# POWER.net
KiCad netlist of a schematic drawn in Altium Designer
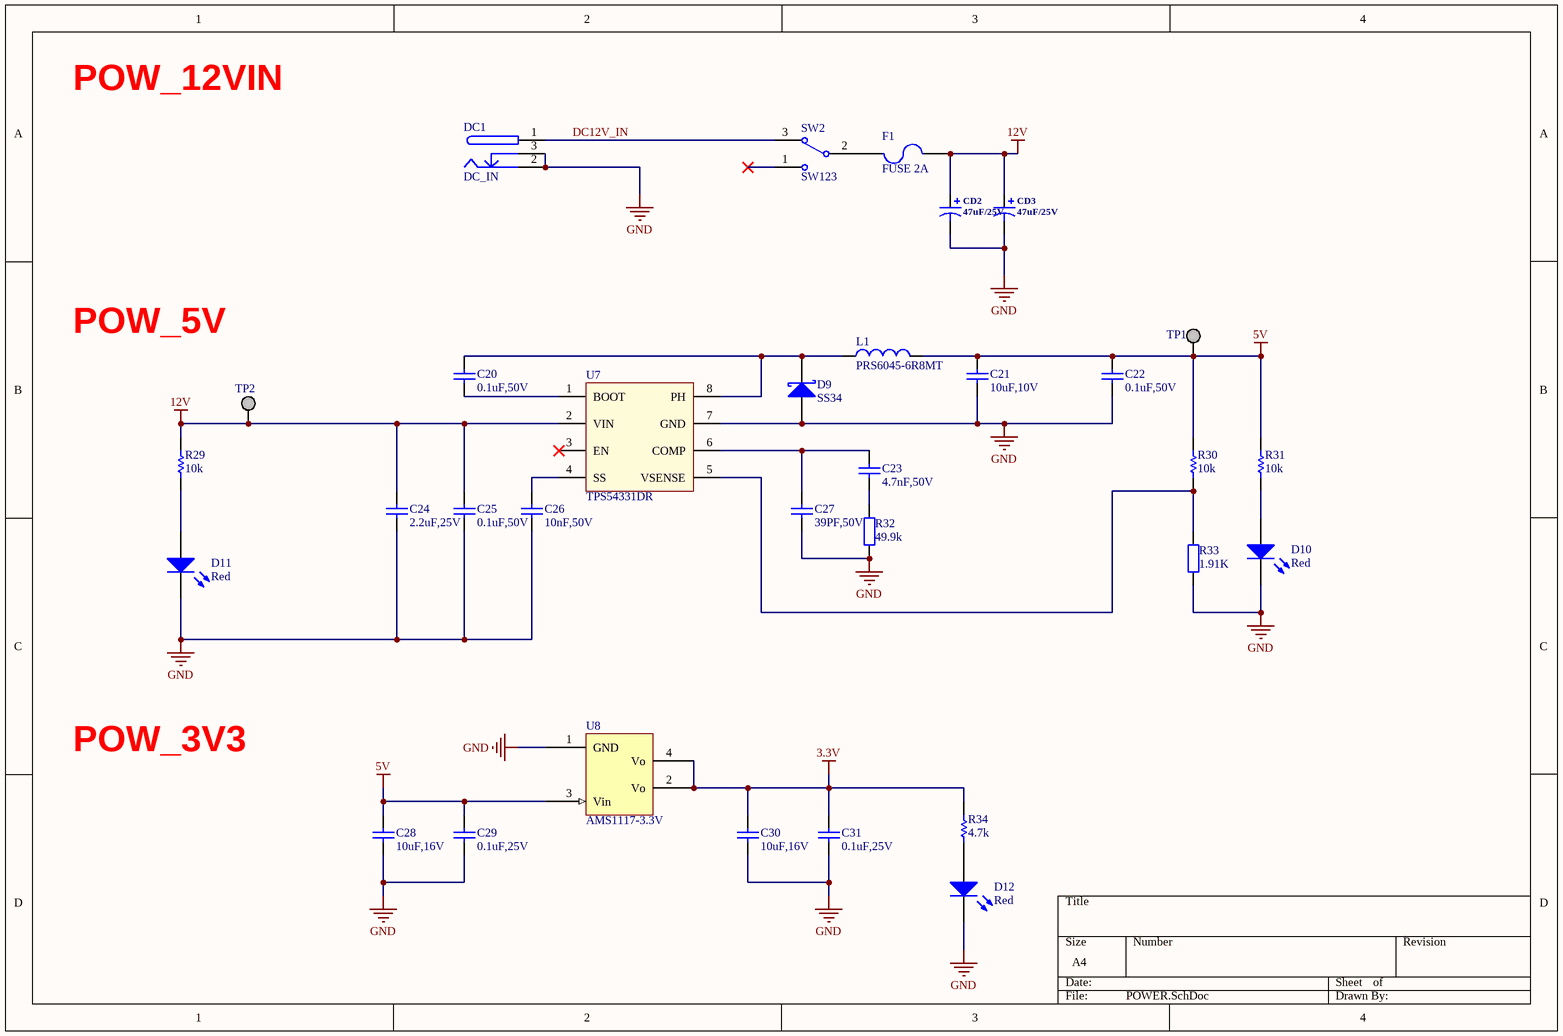
[diagram p0: POWER.SchDoc]

(export (version "E")
  (design (tool "Eeschema 10.0.6"))
  (components
    (comp (ref "C20")
      (value "0.1uF,50V")
      (footprint "0603_C")
      (description "贴片电容")
      (fields (field (name "PART NUMBER") "T_Cap_0603_0.1uF_50V_Y5V") (field (name "TOLERANCE") "20%"))
      (libsource (lib "Database_Library") (part "Cap"))
    )
    (comp (ref "C21")
      (value "10uF,10V")
      (footprint "0603_C")
      (description "贴片电容")
      (fields (field (name "PART NUMBER") "T_Cap_0603_22uF_10V_X5R") (field (name "TOLERANCE") "20%"))
      (libsource (lib "Database_Library") (part "Cap"))
    )
    (comp (ref "C22")
      (value "0.1uF,50V")
      (footprint "0603_C")
      (description "贴片电容")
      (fields (field (name "PART NUMBER") "T_Cap_0603_0.1uF_50V_Y5V") (field (name "TOLERANCE") "20%"))
      (libsource (lib "Database_Library") (part "Cap"))
    )
    (comp (ref "C23")
      (value "4.7nF,50V")
      (footprint "0603_C")
      (description "贴片电容")
      (fields (field (name "PART NUMBER") "T_Cap_0603_4.7nF_50V_X7R") (field (name "TOLERANCE") "10%"))
      (libsource (lib "Database_Library") (part "Cap"))
    )
    (comp (ref "C24")
      (value "2.2uF,25V")
      (footprint "0603_C")
      (description "贴片电容")
      (fields (field (name "PART NUMBER") "T_Cap_0603_2.2uF_25V_Y5V") (field (name "TOLERANCE") "20%"))
      (libsource (lib "Database_Library") (part "Cap"))
    )
    (comp (ref "C25")
      (value "0.1uF,50V")
      (footprint "0603_C")
      (description "贴片电容")
      (fields (field (name "PART NUMBER") "T_Cap_0603_0.1uF_50V_Y5V") (field (name "TOLERANCE") "20%"))
      (libsource (lib "Database_Library") (part "Cap"))
    )
    (comp (ref "C26")
      (value "10nF,50V")
      (footprint "0603_C")
      (description "贴片电容")
      (fields (field (name "PART NUMBER") "T_Cap_0603_10nF_50V_X7R") (field (name "TOLERANCE") "10%"))
      (libsource (lib "Database_Library") (part "Cap"))
    )
    (comp (ref "C27")
      (value "39PF,50V")
      (footprint "0603_C")
      (description "贴片电容")
      (fields (field (name "PART NUMBER") "T_Cap_0603_39PF_50V_C0G") (field (name "TOLERANCE") "5%"))
      (libsource (lib "Database_Library") (part "Cap"))
    )
    (comp (ref "C28")
      (value "10uF,16V")
      (footprint "0603_C")
      (description "贴片电容")
      (fields (field (name "PART NUMBER") "T_Cap_0603_10uF_16V_X5R") (field (name "TOLERANCE") "10%"))
      (libsource (lib "Database_Library") (part "Cap"))
    )
    (comp (ref "C29")
      (value "0.1uF,25V")
      (footprint "0603_C")
      (description "贴片电容")
      (fields (field (name "PART NUMBER") "T_Cap_0603_0.1uF_25V_X5R") (field (name "TOLERANCE") "10%"))
      (libsource (lib "Database_Library") (part "Cap"))
    )
    (comp (ref "C30")
      (value "10uF,16V")
      (footprint "0603_C")
      (description "贴片电容")
      (fields (field (name "PART NUMBER") "T_Cap_0603_10uF_16V_X5R") (field (name "TOLERANCE") "10%"))
      (libsource (lib "Database_Library") (part "Cap"))
    )
    (comp (ref "C31")
      (value "0.1uF,25V")
      (footprint "0603_C")
      (description "贴片电容")
      (fields (field (name "PART NUMBER") "T_Cap_0603_0.1uF_25V_X5R") (field (name "TOLERANCE") "10%"))
      (libsource (lib "Database_Library") (part "Cap"))
    )
    (comp (ref "CD2")
      (value "47uF/25V")
      (footprint "CD7343")
      (description "钽电容,Tantalum Capacitors,47uF/16V,3.5*2.8")
      (fields (field (name "PUBLISHER") "Altium Limited"))
      (libsource (lib "模拟器件") (part "C-100uF/25V"))
    )
    (comp (ref "CD3")
      (value "47uF/25V")
      (footprint "CD7343")
      (description "钽电容,Tantalum Capacitors,47uF/16V,3.5*2.8")
      (fields (field (name "PUBLISHER") "Altium Limited"))
      (libsource (lib "模拟器件") (part "C-100uF/25V"))
    )
    (comp (ref "D9")
      (value "SS34")
      (footprint "DO-214AC")
      (description "肖特基二极管")
      (fields (field (name "PART NUMBER") "T_SS34"))
      (libsource (lib "Database_Library") (part "Diode Schottky"))
    )
    (comp (ref "D10")
      (value "Red")
      (footprint "0603_LED")
      (description "红色LED灯")
      (fields (field (name "PART NUMBER") "T_LED_Red_0805"))
      (libsource (lib "Database_Library") (part "LED"))
    )
    (comp (ref "D11")
      (value "Red")
      (footprint "0603_LED")
      (description "红色LED灯")
      (fields (field (name "PART NUMBER") "T_LED_Red_0805"))
      (libsource (lib "Database_Library") (part "LED"))
    )
    (comp (ref "D12")
      (value "Red")
      (footprint "0603_LED")
      (description "红色LED灯")
      (fields (field (name "PART NUMBER") "T_LED_Red_0805"))
      (libsource (lib "Database_Library") (part "LED"))
    )
    (comp (ref "DC1")
      (value "DC_IN")
      (footprint "PJ-058A")
      (description "DC插座")
      (libsource (lib "aiskylab-14Connectors-19PWRCon") (part "DC_IN"))
    )
    (comp (ref "F1")
      (value "FUSE 2A")
      (footprint "1206_FUSE")
      (description "Fuse")
      (fields (field (name "PUBLISHER") "Altium Limited"))
      (libsource (lib "jinrylib") (part "Fuse 2"))
    )
    (comp (ref "L1")
      (value "PRS6045-6R8MT")
      (footprint "IND-SMD_L5.8-W5.2")
      (description "贴片电感")
      (fields (field (name "PART NUMBER") "T_PRS6045-6R8MT") (field (name "TOLERANCE") "20%"))
      (libsource (lib "Database_Library") (part "Inductors"))
    )
    (comp (ref "R29")
      (value "10k")
      (footprint "0603_R")
      (description "贴片电阻")
      (fields (field (name "PART NUMBER") "T_Res_0603_10k_5%_1/10W") (field (name "POWER") "1/10W"))
      (libsource (lib "Database_Library") (part "Res_5%"))
    )
    (comp (ref "R30")
      (value "10k")
      (footprint "0603_R")
      (description "贴片电阻")
      (fields (field (name "PART NUMBER") "T_Res_0603_10k_5%_1/10W") (field (name "POWER") "1/10W"))
      (libsource (lib "Database_Library") (part "Res_5%"))
    )
    (comp (ref "R31")
      (value "10k")
      (footprint "0603_R")
      (description "贴片电阻")
      (fields (field (name "PART NUMBER") "T_Res_0603_10k_5%_1/10W") (field (name "POWER") "1/10W"))
      (libsource (lib "Database_Library") (part "Res_5%"))
    )
    (comp (ref "R32")
      (value "49.9k")
      (footprint "0603_R")
      (description "贴片电阻")
      (fields (field (name "PART NUMBER") "T_Res_0603_49.9k_1%_1/10W") (field (name "POWER") "1/10W"))
      (libsource (lib "Database_Library") (part "Res"))
    )
    (comp (ref "R33")
      (value "1.91K")
      (footprint "0603_R")
      (description "贴片电阻")
      (fields (field (name "PART NUMBER") "T_Res_0603_1.91k_1%_1/10W") (field (name "POWER") "1/10W"))
      (libsource (lib "Database_Library") (part "Res"))
    )
    (comp (ref "R34")
      (value "4.7k")
      (footprint "0603_R")
      (description "贴片电阻")
      (fields (field (name "PART NUMBER") "T_Res_0603_10k_5%_1/10W") (field (name "POWER") "1/10W"))
      (libsource (lib "Database_Library") (part "Res_5%"))
    )
    (comp (ref "SW2")
      (value "SW123")
      (footprint "SW-TH_SS-12D10L9")
      (description "C319011")
      (libsource (lib "jinrylib") (part "SW123"))
    )
    (comp (ref "TP1")
      (value "T_TestPoint_H")
      (footprint "TP_H")
      (description "测试点_过孔")
      (libsource (lib "Database_Library") (part "TP"))
    )
    (comp (ref "TP2")
      (value "T_TestPoint_H")
      (footprint "TP_H")
      (description "测试点_过孔")
      (libsource (lib "Database_Library") (part "TP"))
    )
    (comp (ref "U7")
      (value "TPS54331DR")
      (footprint "SOIC8")
      (description "TI, 3A, 3.5-28V, Buck")
      (libsource (lib "MyLibrary") (part "TPS54331"))
    )
    (comp (ref "U8")
      (value "AMS1117-3.3V")
      (footprint "SOT223")
      (description "电源芯片")
      (fields (field (name "PART NUMBER") "T_AMS1117-3.3V"))
      (libsource (lib "Database_Library") (part "AMS1117"))
    )
  )
  (nets
    (net (code "1") (name "/DC12V_IN") (class "Default")
      (node (ref "DC1") (pin "1") (pinfunction "1_1") (pintype "passive"))
      (node (ref "SW2") (pin "3") (pinfunction "3_3") (pintype "passive"))
    )
    (net (code "2") (name "3.3V") (class "Default")
      (node (ref "C30") (pin "2") (pinfunction "2_2") (pintype "passive"))
      (node (ref "C31") (pin "2") (pinfunction "2_2") (pintype "passive"))
      (node (ref "R34") (pin "2") (pinfunction "2_2") (pintype "passive"))
      (node (ref "U8") (pin "2") (pinfunction "Vo_2") (pintype "passive"))
      (node (ref "U8") (pin "4") (pinfunction "Vo_4") (pintype "passive"))
    )
    (net (code "3") (name "5V") (class "Default")
      (node (ref "C21") (pin "2") (pinfunction "2_2") (pintype "passive"))
      (node (ref "C22") (pin "2") (pinfunction "2_2") (pintype "passive"))
      (node (ref "C28") (pin "2") (pinfunction "2_2") (pintype "passive"))
      (node (ref "C29") (pin "2") (pinfunction "2_2") (pintype "passive"))
      (node (ref "L1") (pin "2") (pinfunction "2_2") (pintype "passive"))
      (node (ref "R30") (pin "2") (pinfunction "2_2") (pintype "passive"))
      (node (ref "R31") (pin "2") (pinfunction "2_2") (pintype "passive"))
      (node (ref "TP1") (pin "1") (pinfunction "1_1") (pintype "passive"))
      (node (ref "U8") (pin "3") (pinfunction "Vin_3") (pintype "input"))
    )
    (net (code "4") (name "12V") (class "Default")
      (node (ref "C24") (pin "2") (pinfunction "2_2") (pintype "passive"))
      (node (ref "C25") (pin "2") (pinfunction "2_2") (pintype "passive"))
      (node (ref "CD2") (pin "1") (pinfunction "1_1") (pintype "passive"))
      (node (ref "CD3") (pin "1") (pinfunction "1_1") (pintype "passive"))
      (node (ref "F1") (pin "1") (pinfunction "1_1") (pintype "passive"))
      (node (ref "R29") (pin "2") (pinfunction "2_2") (pintype "passive"))
      (node (ref "TP2") (pin "1") (pinfunction "1_1") (pintype "passive"))
      (node (ref "U7") (pin "2") (pinfunction "VIN_2") (pintype "passive"))
    )
    (net (code "5") (name "GND") (class "Default")
      (node (ref "C21") (pin "1") (pinfunction "1_1") (pintype "passive"))
      (node (ref "C22") (pin "1") (pinfunction "1_1") (pintype "passive"))
      (node (ref "C24") (pin "1") (pinfunction "1_1") (pintype "passive"))
      (node (ref "C25") (pin "1") (pinfunction "1_1") (pintype "passive"))
      (node (ref "C26") (pin "2") (pinfunction "2_2") (pintype "passive"))
      (node (ref "C27") (pin "1") (pinfunction "1_1") (pintype "passive"))
      (node (ref "C28") (pin "1") (pinfunction "1_1") (pintype "passive"))
      (node (ref "C29") (pin "1") (pinfunction "1_1") (pintype "passive"))
      (node (ref "C30") (pin "1") (pinfunction "1_1") (pintype "passive"))
      (node (ref "C31") (pin "1") (pinfunction "1_1") (pintype "passive"))
      (node (ref "CD2") (pin "2") (pinfunction "2_2") (pintype "passive"))
      (node (ref "CD3") (pin "2") (pinfunction "2_2") (pintype "passive"))
      (node (ref "D10") (pin "2") (pinfunction "K_2") (pintype "passive"))
      (node (ref "D11") (pin "2") (pinfunction "K_2") (pintype "passive"))
      (node (ref "D12") (pin "2") (pinfunction "K_2") (pintype "passive"))
      (node (ref "D9") (pin "1") (pinfunction "A_1") (pintype "passive"))
      (node (ref "DC1") (pin "2") (pinfunction "2_2") (pintype "passive"))
      (node (ref "DC1") (pin "3") (pinfunction "3_3") (pintype "passive"))
      (node (ref "R32") (pin "1") (pinfunction "1_1") (pintype "passive"))
      (node (ref "R33") (pin "1") (pinfunction "1_1") (pintype "passive"))
      (node (ref "U7") (pin "7") (pinfunction "GND_7") (pintype "passive"))
      (node (ref "U8") (pin "1") (pinfunction "GND_1") (pintype "passive"))
    )
    (net (code "6") (name "Net-(C23-Pad1)") (class "Default")
      (node (ref "C23") (pin "1") (pinfunction "1_1") (pintype "passive"))
      (node (ref "R32") (pin "2") (pinfunction "2_2") (pintype "passive"))
    )
    (net (code "7") (name "Net-(D9-K)") (class "Default")
      (node (ref "C20") (pin "2") (pinfunction "2_2") (pintype "passive"))
      (node (ref "D9") (pin "2") (pinfunction "K_2") (pintype "passive"))
      (node (ref "L1") (pin "1") (pinfunction "1_1") (pintype "passive"))
      (node (ref "U7") (pin "8") (pinfunction "PH_8") (pintype "passive"))
    )
    (net (code "8") (name "Net-(D10-A)") (class "Default")
      (node (ref "D10") (pin "1") (pinfunction "A_1") (pintype "passive"))
      (node (ref "R31") (pin "1") (pinfunction "1_1") (pintype "passive"))
    )
    (net (code "9") (name "Net-(D11-A)") (class "Default")
      (node (ref "D11") (pin "1") (pinfunction "A_1") (pintype "passive"))
      (node (ref "R29") (pin "1") (pinfunction "1_1") (pintype "passive"))
    )
    (net (code "10") (name "Net-(D12-A)") (class "Default")
      (node (ref "D12") (pin "1") (pinfunction "A_1") (pintype "passive"))
      (node (ref "R34") (pin "1") (pinfunction "1_1") (pintype "passive"))
    )
    (net (code "11") (name "Net-(F1-Pad2)") (class "Default")
      (node (ref "F1") (pin "2") (pinfunction "2_2") (pintype "passive"))
      (node (ref "SW2") (pin "2") (pinfunction "2_2") (pintype "passive"))
    )
    (net (code "12") (name "Net-(U7-BOOT)") (class "Default")
      (node (ref "C20") (pin "1") (pinfunction "1_1") (pintype "passive"))
      (node (ref "U7") (pin "1") (pinfunction "BOOT_1") (pintype "passive"))
    )
    (net (code "13") (name "Net-(U7-COMP)") (class "Default")
      (node (ref "C23") (pin "2") (pinfunction "2_2") (pintype "passive"))
      (node (ref "C27") (pin "2") (pinfunction "2_2") (pintype "passive"))
      (node (ref "U7") (pin "6") (pinfunction "COMP_6") (pintype "passive"))
    )
    (net (code "14") (name "Net-(U7-SS)") (class "Default")
      (node (ref "C26") (pin "1") (pinfunction "1_1") (pintype "passive"))
      (node (ref "U7") (pin "4") (pinfunction "SS_4") (pintype "passive"))
    )
    (net (code "15") (name "Net-(U7-VSENSE)") (class "Default")
      (node (ref "R30") (pin "1") (pinfunction "1_1") (pintype "passive"))
      (node (ref "R33") (pin "2") (pinfunction "2_2") (pintype "passive"))
      (node (ref "U7") (pin "5") (pinfunction "VSENSE_5") (pintype "passive"))
    )
    (net (code "16") (name "unconnected-(SW2-Pad1)") (class "Default")
      (node (ref "SW2") (pin "1") (pinfunction "1_1") (pintype "passive+no_connect"))
    )
    (net (code "17") (name "unconnected-(U7-EN-Pad3)") (class "Default")
      (node (ref "U7") (pin "3") (pinfunction "EN_3") (pintype "passive+no_connect"))
    )
  )
)
